# untitled.net
KiCad netlist of a schematic drawn in EAGLE
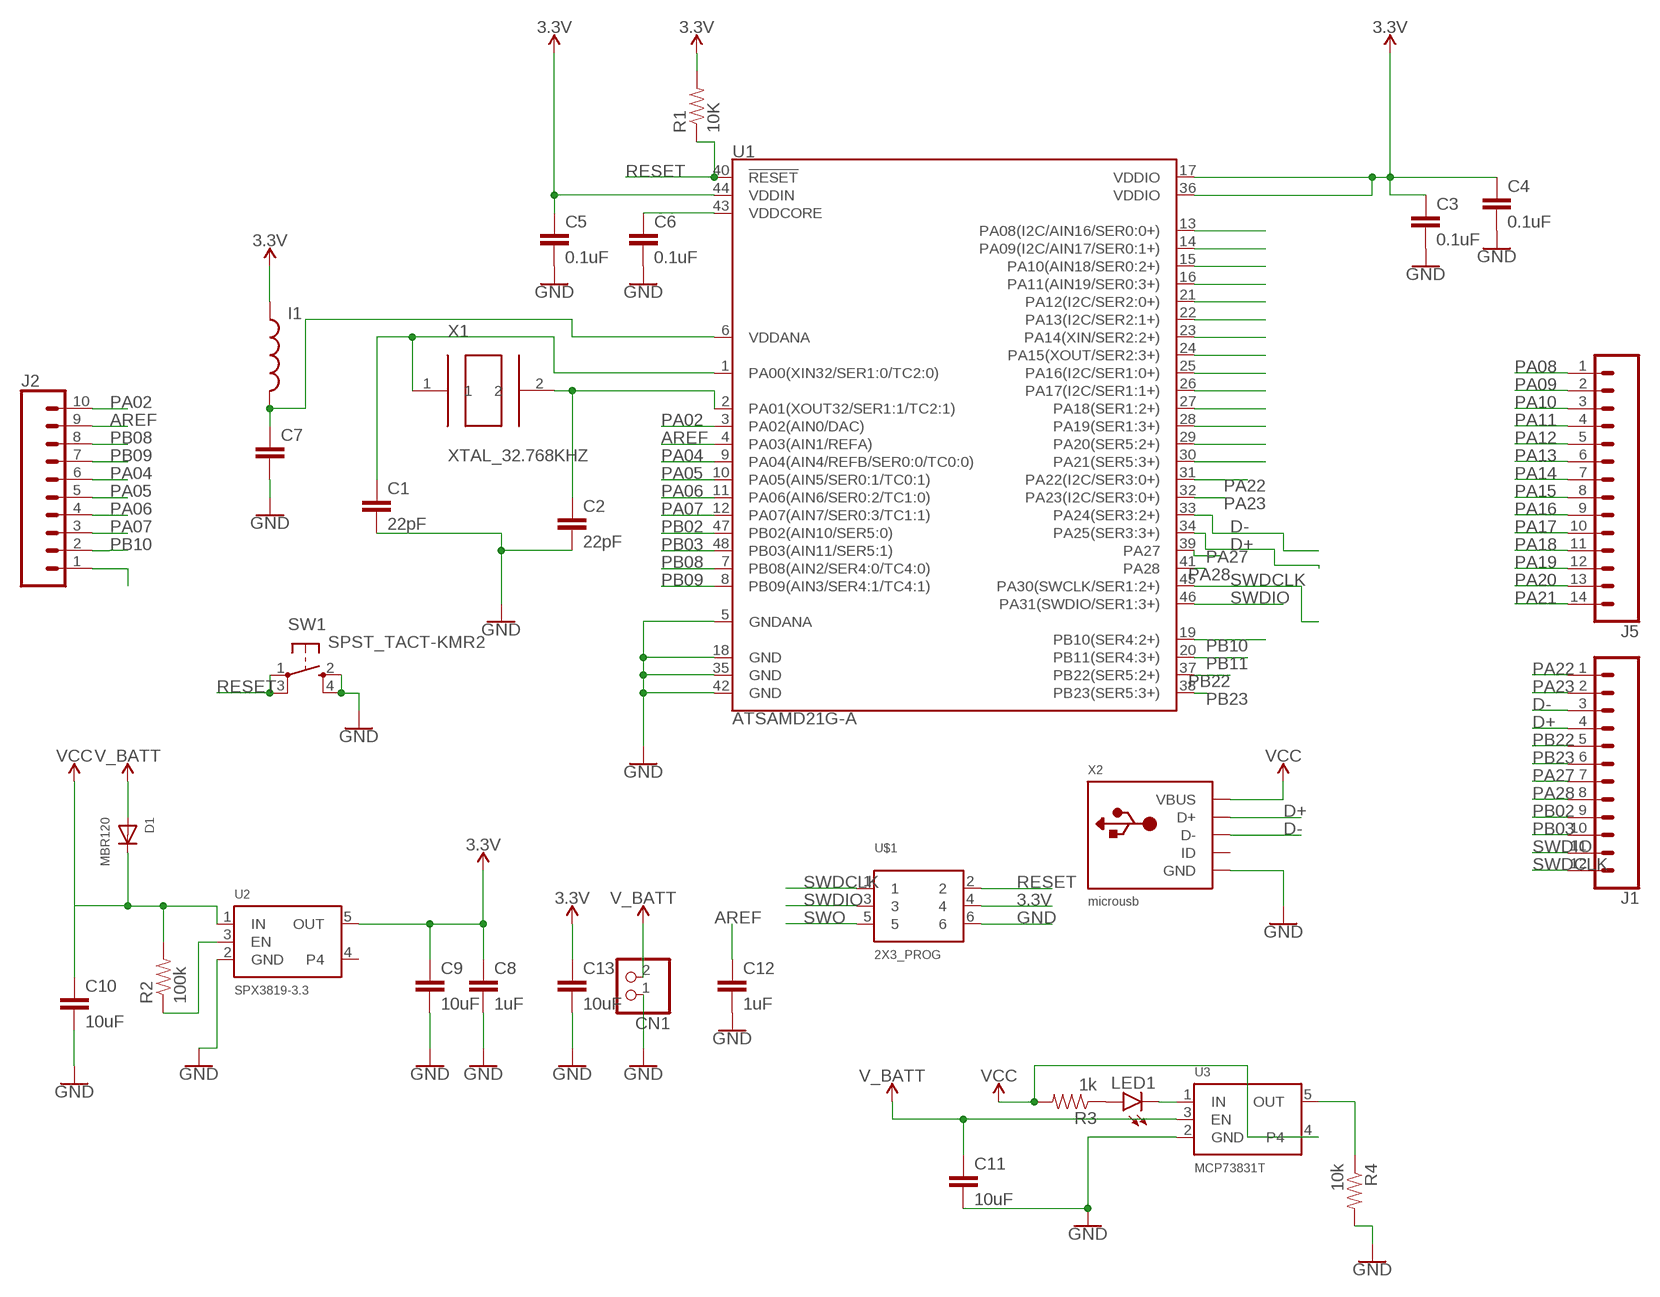
[diagram p0: schematic, sheet 1]

(export (version "E")
  (design (tool "Eeschema 10.0.6"))
  (components
    (comp (ref "C1")
      (value "22pF")
      (footprint "eagle-import:0805")
      (libsource (lib "eagle-import") (part "CAP"))
    )
    (comp (ref "C2")
      (value "22pF")
      (footprint "eagle-import:0805")
      (libsource (lib "eagle-import") (part "CAP"))
    )
    (comp (ref "C3")
      (value "0.1uF")
      (footprint "eagle-import:0805")
      (libsource (lib "eagle-import") (part "CAP"))
    )
    (comp (ref "C4")
      (value "0.1uF")
      (footprint "eagle-import:0805")
      (libsource (lib "eagle-import") (part "CAP"))
    )
    (comp (ref "C5")
      (value "0.1uF")
      (footprint "eagle-import:0805")
      (libsource (lib "eagle-import") (part "CAP"))
    )
    (comp (ref "C6")
      (value "0.1uF")
      (footprint "eagle-import:0805")
      (libsource (lib "eagle-import") (part "CAP"))
    )
    (comp (ref "C7")
      (value "CAP")
      (footprint "eagle-import:0805")
      (libsource (lib "eagle-import") (part "CAP"))
    )
    (comp (ref "C8")
      (value "1uF")
      (footprint "eagle-import:0805")
      (libsource (lib "eagle-import") (part "CAP"))
    )
    (comp (ref "C9")
      (value "10uF")
      (footprint "eagle-import:0805")
      (libsource (lib "eagle-import") (part "CAP"))
    )
    (comp (ref "C10")
      (value "10uF")
      (footprint "eagle-import:0805")
      (libsource (lib "eagle-import") (part "CAP"))
    )
    (comp (ref "C11")
      (value "10uF")
      (footprint "eagle-import:0805")
      (libsource (lib "eagle-import") (part "CAP"))
    )
    (comp (ref "C12")
      (value "1uF")
      (footprint "eagle-import:0805")
      (libsource (lib "eagle-import") (part "CAP"))
    )
    (comp (ref "C13")
      (value "10uF")
      (footprint "eagle-import:0805")
      (libsource (lib "eagle-import") (part "CAP"))
    )
    (comp (ref "CN1")
      (value "JST_2PIN")
      (footprint "eagle-import:JSTPH2")
      (libsource (lib "eagle-import") (part "JST_2PIN"))
    )
    (comp (ref "D1")
      (value "MBR120")
      (footprint "eagle-import:SOD-123")
      (libsource (lib "eagle-import") (part "DIODESOD-123"))
    )
    (comp (ref "I1")
      (value "IND")
      (footprint "eagle-import:0805")
      (libsource (lib "eagle-import") (part "IND"))
    )
    (comp (ref "J1")
      (value "CONN_12")
      (footprint "eagle-import:1X12")
      (libsource (lib "eagle-import") (part "CONN_12"))
    )
    (comp (ref "J2")
      (value "CONN_10\"")
      (footprint "eagle-import:1X10")
      (libsource (lib "eagle-import") (part "CONN_10{dblquote}"))
    )
    (comp (ref "J5")
      (value "CONN_14")
      (footprint "eagle-import:1X14")
      (libsource (lib "eagle-import") (part "CONN_14"))
    )
    (comp (ref "LED1")
      (value "LED0603")
      (footprint "eagle-import:LED-0603")
      (libsource (lib "eagle-import") (part "LED0603"))
    )
    (comp (ref "R1")
      (value "10K")
      (footprint "eagle-import:0805")
      (libsource (lib "eagle-import") (part "RES"))
    )
    (comp (ref "R2")
      (value "100k")
      (footprint "eagle-import:0805")
      (libsource (lib "eagle-import") (part "RES"))
    )
    (comp (ref "R3")
      (value "1k")
      (footprint "eagle-import:0805")
      (libsource (lib "eagle-import") (part "RES"))
    )
    (comp (ref "R4")
      (value "10k")
      (footprint "eagle-import:0805")
      (libsource (lib "eagle-import") (part "RES"))
    )
    (comp (ref "SW1")
      (value "SPST_TACT-KMR2")
      (footprint "eagle-import:KMR2")
      (libsource (lib "eagle-import") (part "SPST_TACT-KMR2"))
    )
    (comp (ref "U$1")
      (value "2X3_PROG")
      (footprint "eagle-import:2X3-SMD_PROG")
      (libsource (lib "eagle-import") (part "2X3_PROG"))
    )
    (comp (ref "U1")
      (value "ATSAMD21G-A")
      (footprint "eagle-import:TQFP-48")
      (libsource (lib "eagle-import") (part "ATSAMD21G-A"))
    )
    (comp (ref "U2")
      (value "SPX3819-3.3")
      (footprint "eagle-import:SOT23-5")
      (libsource (lib "eagle-import") (part "VREG_SOT23-5"))
    )
    (comp (ref "U3")
      (value "MCP73831T")
      (footprint "eagle-import:SOT23-5")
      (libsource (lib "eagle-import") (part "VREG_SOT23-5"))
    )
    (comp (ref "X1")
      (value "XTAL_32.768KHZ")
      (footprint "eagle-import:ABS07-32.768KHZ-9-T")
      (libsource (lib "eagle-import") (part "XTAL_32.768KHZ"))
    )
    (comp (ref "X2")
      (value "microusb")
      (footprint "eagle-import:4UCONN_20329_V2")
      (libsource (lib "eagle-import") (part "USB_MICRO_20329_V2"))
    )
  )
  (nets
    (net (code "1") (name "/AREF") (class "Default")
      (node (ref "C12") (pin "1") (pinfunction "1_1") (pintype "passive"))
      (node (ref "J2") (pin "9") (pinfunction "9_9") (pintype "passive"))
      (node (ref "U1") (pin "4") (pinfunction "PA03(AIN1/REFA)_4") (pintype "bidirectional"))
    )
    (net (code "2") (name "/D+") (class "Default")
      (node (ref "J1") (pin "4") (pinfunction "4_4") (pintype "passive"))
      (node (ref "U1") (pin "34") (pinfunction "PA25(SER3:3+)_34") (pintype "bidirectional"))
      (node (ref "X2") (pin "D+") (pinfunction "D+_D+") (pintype "bidirectional"))
    )
    (net (code "3") (name "/D-") (class "Default")
      (node (ref "J1") (pin "3") (pinfunction "3_3") (pintype "passive"))
      (node (ref "U1") (pin "33") (pinfunction "PA24(SER3:2+)_33") (pintype "bidirectional"))
      (node (ref "X2") (pin "D-") (pinfunction "D-_D-") (pintype "bidirectional"))
    )
    (net (code "4") (name "/PA02") (class "Default")
      (node (ref "J2") (pin "10") (pinfunction "10_10") (pintype "passive"))
      (node (ref "U1") (pin "3") (pinfunction "PA02(AIN0/DAC)_3") (pintype "bidirectional"))
    )
    (net (code "5") (name "/PA04") (class "Default")
      (node (ref "J2") (pin "6") (pinfunction "6_6") (pintype "passive"))
      (node (ref "U1") (pin "9") (pinfunction "PA04(AIN4/REFB/SER0:0/TC0:0)_9") (pintype "bidirectional"))
    )
    (net (code "6") (name "/PA05") (class "Default")
      (node (ref "J2") (pin "5") (pinfunction "5_5") (pintype "passive"))
      (node (ref "U1") (pin "10") (pinfunction "PA05(AIN5/SER0:1/TC0:1)_10") (pintype "bidirectional"))
    )
    (net (code "7") (name "/PA06") (class "Default")
      (node (ref "J2") (pin "4") (pinfunction "4_4") (pintype "passive"))
      (node (ref "U1") (pin "11") (pinfunction "PA06(AIN6/SER0:2/TC1:0)_11") (pintype "bidirectional"))
    )
    (net (code "8") (name "/PA07") (class "Default")
      (node (ref "J2") (pin "3") (pinfunction "3_3") (pintype "passive"))
      (node (ref "U1") (pin "12") (pinfunction "PA07(AIN7/SER0:3/TC1:1)_12") (pintype "bidirectional"))
    )
    (net (code "9") (name "/PA08") (class "Default")
      (node (ref "J5") (pin "1") (pinfunction "1_1") (pintype "passive"))
      (node (ref "U1") (pin "13") (pinfunction "PA08(I2C/AIN16/SER0:0+)_13") (pintype "bidirectional"))
    )
    (net (code "10") (name "/PA09") (class "Default")
      (node (ref "J5") (pin "2") (pinfunction "2_2") (pintype "passive"))
      (node (ref "U1") (pin "14") (pinfunction "PA09(I2C/AIN17/SER0:1+)_14") (pintype "bidirectional"))
    )
    (net (code "11") (name "/PA10") (class "Default")
      (node (ref "J5") (pin "3") (pinfunction "3_3") (pintype "passive"))
      (node (ref "U1") (pin "15") (pinfunction "PA10(AIN18/SER0:2+)_15") (pintype "bidirectional"))
    )
    (net (code "12") (name "/PA11") (class "Default")
      (node (ref "J5") (pin "4") (pinfunction "4_4") (pintype "passive"))
      (node (ref "U1") (pin "16") (pinfunction "PA11(AIN19/SER0:3+)_16") (pintype "bidirectional"))
    )
    (net (code "13") (name "/PA12") (class "Default")
      (node (ref "J5") (pin "5") (pinfunction "5_5") (pintype "passive"))
      (node (ref "U1") (pin "21") (pinfunction "PA12(I2C/SER2:0+)_21") (pintype "bidirectional"))
    )
    (net (code "14") (name "/PA13") (class "Default")
      (node (ref "J5") (pin "6") (pinfunction "6_6") (pintype "passive"))
      (node (ref "U1") (pin "22") (pinfunction "PA13(I2C/SER2:1+)_22") (pintype "bidirectional"))
    )
    (net (code "15") (name "/PA14") (class "Default")
      (node (ref "J5") (pin "7") (pinfunction "7_7") (pintype "passive"))
      (node (ref "U1") (pin "23") (pinfunction "PA14(XIN/SER2:2+)_23") (pintype "bidirectional"))
    )
    (net (code "16") (name "/PA15") (class "Default")
      (node (ref "J5") (pin "8") (pinfunction "8_8") (pintype "passive"))
      (node (ref "U1") (pin "24") (pinfunction "PA15(XOUT/SER2:3+)_24") (pintype "bidirectional"))
    )
    (net (code "17") (name "/PA16") (class "Default")
      (node (ref "J5") (pin "9") (pinfunction "9_9") (pintype "passive"))
      (node (ref "U1") (pin "25") (pinfunction "PA16(I2C/SER1:0+)_25") (pintype "bidirectional"))
    )
    (net (code "18") (name "/PA17") (class "Default")
      (node (ref "J5") (pin "10") (pinfunction "10_10") (pintype "passive"))
      (node (ref "U1") (pin "26") (pinfunction "PA17(I2C/SER1:1+)_26") (pintype "bidirectional"))
    )
    (net (code "19") (name "/PA18") (class "Default")
      (node (ref "J5") (pin "11") (pinfunction "11_11") (pintype "passive"))
      (node (ref "U1") (pin "27") (pinfunction "PA18(SER1:2+)_27") (pintype "bidirectional"))
    )
    (net (code "20") (name "/PA19") (class "Default")
      (node (ref "J5") (pin "12") (pinfunction "12_12") (pintype "passive"))
      (node (ref "U1") (pin "28") (pinfunction "PA19(SER1:3+)_28") (pintype "bidirectional"))
    )
    (net (code "21") (name "/PA20") (class "Default")
      (node (ref "J5") (pin "13") (pinfunction "13_13") (pintype "passive"))
      (node (ref "U1") (pin "29") (pinfunction "PA20(SER5:2+)_29") (pintype "bidirectional"))
    )
    (net (code "22") (name "/PA21") (class "Default")
      (node (ref "J5") (pin "14") (pinfunction "14_14") (pintype "passive"))
      (node (ref "U1") (pin "30") (pinfunction "PA21(SER5:3+)_30") (pintype "bidirectional"))
    )
    (net (code "23") (name "/PA22") (class "Default")
      (node (ref "J1") (pin "1") (pinfunction "1_1") (pintype "passive"))
      (node (ref "U1") (pin "31") (pinfunction "PA22(I2C/SER3:0+)_31") (pintype "bidirectional"))
    )
    (net (code "24") (name "/PA23") (class "Default")
      (node (ref "J1") (pin "2") (pinfunction "2_2") (pintype "passive"))
      (node (ref "U1") (pin "32") (pinfunction "PA23(I2C/SER3:0+)_32") (pintype "bidirectional"))
    )
    (net (code "25") (name "/PA27") (class "Default")
      (node (ref "J1") (pin "7") (pinfunction "7_7") (pintype "passive"))
      (node (ref "U1") (pin "39") (pinfunction "PA27_39") (pintype "bidirectional"))
    )
    (net (code "26") (name "/PA28") (class "Default")
      (node (ref "J1") (pin "8") (pinfunction "8_8") (pintype "passive"))
      (node (ref "U1") (pin "41") (pinfunction "PA28_41") (pintype "bidirectional"))
    )
    (net (code "27") (name "/PB02") (class "Default")
      (node (ref "J1") (pin "9") (pinfunction "9_9") (pintype "passive"))
      (node (ref "U1") (pin "47") (pinfunction "PB02(AIN10/SER5:0)_47") (pintype "bidirectional"))
    )
    (net (code "28") (name "/PB03") (class "Default")
      (node (ref "J1") (pin "10") (pinfunction "10_10") (pintype "passive"))
      (node (ref "U1") (pin "48") (pinfunction "PB03(AIN11/SER5:1)_48") (pintype "bidirectional"))
    )
    (net (code "29") (name "/PB08") (class "Default")
      (node (ref "J2") (pin "8") (pinfunction "8_8") (pintype "passive"))
      (node (ref "U1") (pin "7") (pinfunction "PB08(AIN2/SER4:0/TC4:0)_7") (pintype "bidirectional"))
    )
    (net (code "30") (name "/PB09") (class "Default")
      (node (ref "J2") (pin "7") (pinfunction "7_7") (pintype "passive"))
      (node (ref "U1") (pin "8") (pinfunction "PB09(AIN3/SER4:1/TC4:1)_8") (pintype "bidirectional"))
    )
    (net (code "31") (name "/PB10") (class "Default")
      (node (ref "J2") (pin "2") (pinfunction "2_2") (pintype "passive"))
      (node (ref "U1") (pin "19") (pinfunction "PB10(SER4:2+)_19") (pintype "bidirectional"))
    )
    (net (code "32") (name "/PB11") (class "Default")
      (node (ref "J2") (pin "1") (pinfunction "1_1") (pintype "passive"))
      (node (ref "U1") (pin "20") (pinfunction "PB11(SER4:3+)_20") (pintype "bidirectional"))
    )
    (net (code "33") (name "/PB22") (class "Default")
      (node (ref "J1") (pin "5") (pinfunction "5_5") (pintype "passive"))
      (node (ref "U1") (pin "37") (pinfunction "PB22(SER5:2+)_37") (pintype "bidirectional"))
    )
    (net (code "34") (name "/PB23") (class "Default")
      (node (ref "J1") (pin "6") (pinfunction "6_6") (pintype "passive"))
      (node (ref "U1") (pin "38") (pinfunction "PB23(SER5:3+)_38") (pintype "bidirectional"))
    )
    (net (code "35") (name "/RESET") (class "Default")
      (node (ref "R1") (pin "1") (pinfunction "1_1") (pintype "passive"))
      (node (ref "SW1") (pin "1") (pinfunction "P_1") (pintype "passive"))
      (node (ref "SW1") (pin "3") (pinfunction "P1_3") (pintype "passive"))
      (node (ref "U$1") (pin "2") (pinfunction "2_2") (pintype "bidirectional"))
      (node (ref "U1") (pin "40") (pinfunction "~{RESET}_40") (pintype "bidirectional"))
    )
    (net (code "36") (name "/SWDCLK") (class "Default")
      (node (ref "J1") (pin "12") (pinfunction "12_12") (pintype "passive"))
      (node (ref "U$1") (pin "1") (pinfunction "1_1") (pintype "bidirectional"))
      (node (ref "U1") (pin "45") (pinfunction "PA30(SWCLK/SER1:2+)_45") (pintype "bidirectional"))
    )
    (net (code "37") (name "/SWDIO") (class "Default")
      (node (ref "J1") (pin "11") (pinfunction "11_11") (pintype "passive"))
      (node (ref "U$1") (pin "3") (pinfunction "3_3") (pintype "bidirectional"))
      (node (ref "U1") (pin "46") (pinfunction "PA31(SWDIO/SER1:3+)_46") (pintype "bidirectional"))
    )
    (net (code "38") (name "/SWO") (class "Default")
      (node (ref "U$1") (pin "5") (pinfunction "5_5") (pintype "bidirectional"))
    )
    (net (code "39") (name "3.3V") (class "Default")
      (node (ref "C13") (pin "1") (pinfunction "1_1") (pintype "passive"))
      (node (ref "C3") (pin "1") (pinfunction "1_1") (pintype "passive"))
      (node (ref "C4") (pin "1") (pinfunction "1_1") (pintype "passive"))
      (node (ref "C5") (pin "1") (pinfunction "1_1") (pintype "passive"))
      (node (ref "C8") (pin "1") (pinfunction "1_1") (pintype "passive"))
      (node (ref "C9") (pin "1") (pinfunction "1_1") (pintype "passive"))
      (node (ref "I1") (pin "1") (pinfunction "1_1") (pintype "passive"))
      (node (ref "R1") (pin "2") (pinfunction "2_2") (pintype "passive"))
      (node (ref "U$1") (pin "4") (pinfunction "4_4") (pintype "bidirectional"))
      (node (ref "U1") (pin "17") (pinfunction "VDDIO_17") (pintype "bidirectional"))
      (node (ref "U1") (pin "36") (pinfunction "VDDIO_36") (pintype "bidirectional"))
      (node (ref "U1") (pin "44") (pinfunction "VDDIN_44") (pintype "bidirectional"))
      (node (ref "U2") (pin "5") (pinfunction "OUT_5") (pintype "bidirectional"))
    )
    (net (code "40") (name "GND") (class "Default")
      (node (ref "C1") (pin "2") (pinfunction "2_2") (pintype "passive"))
      (node (ref "C10") (pin "2") (pinfunction "2_2") (pintype "passive"))
      (node (ref "C11") (pin "2") (pinfunction "2_2") (pintype "passive"))
      (node (ref "C12") (pin "2") (pinfunction "2_2") (pintype "passive"))
      (node (ref "C13") (pin "2") (pinfunction "2_2") (pintype "passive"))
      (node (ref "C2") (pin "2") (pinfunction "2_2") (pintype "passive"))
      (node (ref "C3") (pin "2") (pinfunction "2_2") (pintype "passive"))
      (node (ref "C4") (pin "2") (pinfunction "2_2") (pintype "passive"))
      (node (ref "C5") (pin "2") (pinfunction "2_2") (pintype "passive"))
      (node (ref "C6") (pin "2") (pinfunction "2_2") (pintype "passive"))
      (node (ref "C7") (pin "2") (pinfunction "2_2") (pintype "passive"))
      (node (ref "C8") (pin "2") (pinfunction "2_2") (pintype "passive"))
      (node (ref "C9") (pin "2") (pinfunction "2_2") (pintype "passive"))
      (node (ref "CN1") (pin "1") (pinfunction "1_1") (pintype "passive"))
      (node (ref "R4") (pin "2") (pinfunction "2_2") (pintype "passive"))
      (node (ref "SW1") (pin "2") (pinfunction "S_2") (pintype "passive"))
      (node (ref "SW1") (pin "4") (pinfunction "S1_4") (pintype "passive"))
      (node (ref "U$1") (pin "6") (pinfunction "6_6") (pintype "bidirectional"))
      (node (ref "U1") (pin "18") (pinfunction "GND_18") (pintype "bidirectional"))
      (node (ref "U1") (pin "35") (pinfunction "GND_35") (pintype "bidirectional"))
      (node (ref "U1") (pin "42") (pinfunction "GND_42") (pintype "bidirectional"))
      (node (ref "U1") (pin "5") (pinfunction "GNDANA_5") (pintype "bidirectional"))
      (node (ref "U2") (pin "2") (pinfunction "GND_2") (pintype "bidirectional"))
      (node (ref "U3") (pin "2") (pinfunction "GND_2") (pintype "bidirectional"))
      (node (ref "X2") (pin "BASE@1") (pinfunction "GND_BASE@1") (pintype "power_in"))
      (node (ref "X2") (pin "BASE@2") (pinfunction "GND_BASE@2") (pintype "power_in"))
      (node (ref "X2") (pin "GND") (pinfunction "GND_GND") (pintype "power_in"))
      (node (ref "X2") (pin "SPRT@1") (pinfunction "GND_SPRT@1") (pintype "power_in"))
      (node (ref "X2") (pin "SPRT@2") (pinfunction "GND_SPRT@2") (pintype "power_in"))
      (node (ref "X2") (pin "SPRT@3") (pinfunction "GND_SPRT@3") (pintype "power_in"))
      (node (ref "X2") (pin "SPRT@4") (pinfunction "GND_SPRT@4") (pintype "power_in"))
    )
    (net (code "41") (name "Net-(LED1-PadA)") (class "Default")
      (node (ref "LED1") (pin "A") (pinfunction "A_A") (pintype "passive"))
      (node (ref "R3") (pin "1") (pinfunction "1_1") (pintype "passive"))
    )
    (net (code "42") (name "Net-(U1-PA00(XIN32{slash}SER1:0{slash}TC2:0))") (class "Default")
      (node (ref "C1") (pin "1") (pinfunction "1_1") (pintype "passive"))
      (node (ref "U1") (pin "1") (pinfunction "PA00(XIN32/SER1:0/TC2:0)_1") (pintype "bidirectional"))
      (node (ref "X1") (pin "1") (pinfunction "1_1") (pintype "bidirectional"))
    )
    (net (code "43") (name "Net-(U1-PA01(XOUT32{slash}SER1:1{slash}TC2:1))") (class "Default")
      (node (ref "C2") (pin "1") (pinfunction "1_1") (pintype "passive"))
      (node (ref "U1") (pin "2") (pinfunction "PA01(XOUT32/SER1:1/TC2:1)_2") (pintype "bidirectional"))
      (node (ref "X1") (pin "2") (pinfunction "2_2") (pintype "bidirectional"))
    )
    (net (code "44") (name "Net-(U1-VDDANA)") (class "Default")
      (node (ref "C7") (pin "1") (pinfunction "1_1") (pintype "passive"))
      (node (ref "I1") (pin "2") (pinfunction "2_2") (pintype "passive"))
      (node (ref "U1") (pin "6") (pinfunction "VDDANA_6") (pintype "bidirectional"))
    )
    (net (code "45") (name "Net-(U1-VDDCORE)") (class "Default")
      (node (ref "C6") (pin "1") (pinfunction "1_1") (pintype "passive"))
      (node (ref "U1") (pin "43") (pinfunction "VDDCORE_43") (pintype "bidirectional"))
    )
    (net (code "46") (name "Net-(U2-EN)") (class "Default")
      (node (ref "R2") (pin "1") (pinfunction "1_1") (pintype "passive"))
      (node (ref "U2") (pin "3") (pinfunction "EN_3") (pintype "bidirectional"))
    )
    (net (code "47") (name "Net-(U3-IN)") (class "Default")
      (node (ref "LED1") (pin "C") (pinfunction "C_C") (pintype "passive"))
      (node (ref "U3") (pin "1") (pinfunction "IN_1") (pintype "bidirectional"))
    )
    (net (code "48") (name "Net-(U3-OUT)") (class "Default")
      (node (ref "R4") (pin "1") (pinfunction "1_1") (pintype "passive"))
      (node (ref "U3") (pin "5") (pinfunction "OUT_5") (pintype "bidirectional"))
    )
    (net (code "49") (name "VCC") (class "Default")
      (node (ref "C10") (pin "1") (pinfunction "1_1") (pintype "passive"))
      (node (ref "D1") (pin "C") (pinfunction "C_C") (pintype "passive"))
      (node (ref "R2") (pin "2") (pinfunction "2_2") (pintype "passive"))
      (node (ref "R3") (pin "2") (pinfunction "2_2") (pintype "passive"))
      (node (ref "U2") (pin "1") (pinfunction "IN_1") (pintype "bidirectional"))
      (node (ref "U3") (pin "4") (pinfunction "P4_4") (pintype "bidirectional"))
      (node (ref "X2") (pin "VBUS") (pinfunction "VBUS_VBUS") (pintype "power_in"))
    )
    (net (code "50") (name "V_BATT") (class "Default")
      (node (ref "C11") (pin "1") (pinfunction "1_1") (pintype "passive"))
      (node (ref "CN1") (pin "2") (pinfunction "2_2") (pintype "passive"))
      (node (ref "D1") (pin "A") (pinfunction "A_A") (pintype "passive"))
      (node (ref "U3") (pin "3") (pinfunction "EN_3") (pintype "bidirectional"))
    )
    (net (code "51") (name "unconnected-(U2-P4-Pad4)") (class "Default")
      (node (ref "U2") (pin "4") (pinfunction "P4_4") (pintype "bidirectional"))
    )
    (net (code "52") (name "unconnected-(X2-PadID)") (class "Default")
      (node (ref "X2") (pin "ID") (pinfunction "ID_ID") (pintype "bidirectional"))
    )
  )
)
